# GSB-S04-SensorMicrofit.net
KiCad netlist of a schematic drawn in Altium Designer
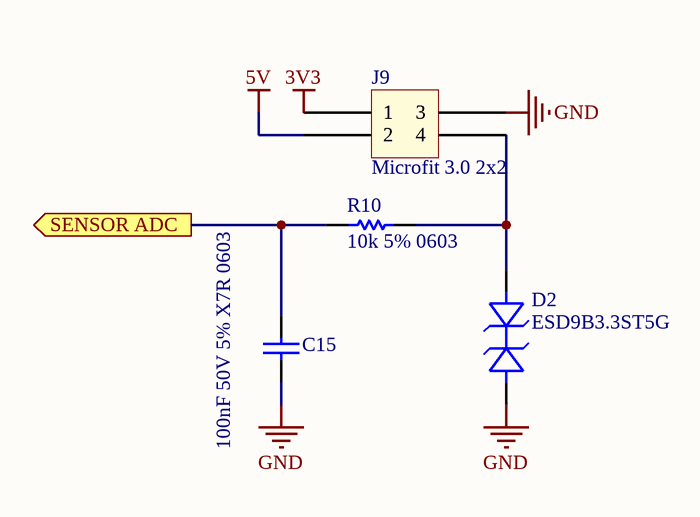
[diagram p0: GSB-S04-SensorMicrofit.SchDoc]

(export (version "E")
  (design (tool "Eeschema 10.0.6"))
  (components
    (comp (ref "C15")
      (value "100nF 50V 5% X7R 0603")
      (footprint "Cap_Ceramic_0603")
      (description "Capacitor, Ceramic, SMD, 100nF, 50V, 5%, X7R, 0603")
      (libsource (lib "StandardCapacitors") (part "100nF 50V 5% X7R 0603"))
    )
    (comp (ref "D2")
      (value "ESD9B3.3ST5G")
      (footprint "SOD-923")
      (description "11.5V Clamp 2A (8/20µs) Ipp Tvs Diode Surface Mount SOD-923")
      (fields (field (name "MANUFACTURER") "ON Semiconductor"))
      (libsource (lib "QUTMS_DiodeLibrary") (part "ESD9B3.3ST5G"))
    )
    (comp (ref "J9")
      (value "Microfit 3.0 2x2")
      (footprint "Microfit_2X2_R_TH")
      (libsource (lib "QUTMS_MicrofitLibrary") (part "Microfit_2x2"))
    )
    (comp (ref "R10")
      (value "10k 5% 0603")
      (footprint "Res_ThinFilm_0603")
      (description "Resistor, SMD, 10k, 0.1W, 5%, 0603")
      (libsource (lib "StandardResistors") (part "10k 5% 0603"))
    )
  )
  (nets
    (net (code "1") (name "/SENSOR ADC") (class "Default")
      (node (ref "C15") (pin "2") (pinfunction "2_2") (pintype "passive"))
      (node (ref "R10") (pin "1") (pinfunction "1_1") (pintype "passive"))
    )
    (net (code "2") (name "3V3") (class "Default")
      (node (ref "J9") (pin "1") (pinfunction "1_1") (pintype "passive"))
    )
    (net (code "3") (name "5V") (class "Default")
      (node (ref "J9") (pin "2") (pinfunction "2_2") (pintype "passive"))
    )
    (net (code "4") (name "GND") (class "Default")
      (node (ref "C15") (pin "1") (pinfunction "1_1") (pintype "passive"))
      (node (ref "D2") (pin "1") (pinfunction "1_1") (pintype "passive"))
      (node (ref "J9") (pin "3") (pinfunction "3_3") (pintype "passive"))
    )
    (net (code "5") (name "Net-(D2-Pad2)") (class "Default")
      (node (ref "D2") (pin "2") (pinfunction "2_2") (pintype "passive"))
      (node (ref "J9") (pin "4") (pinfunction "4_4") (pintype "passive"))
      (node (ref "R10") (pin "2") (pinfunction "2_2") (pintype "passive"))
    )
  )
)
